# matrix_segmen_shalat_v1_3A.net
KiCad netlist of a schematic drawn in EAGLE
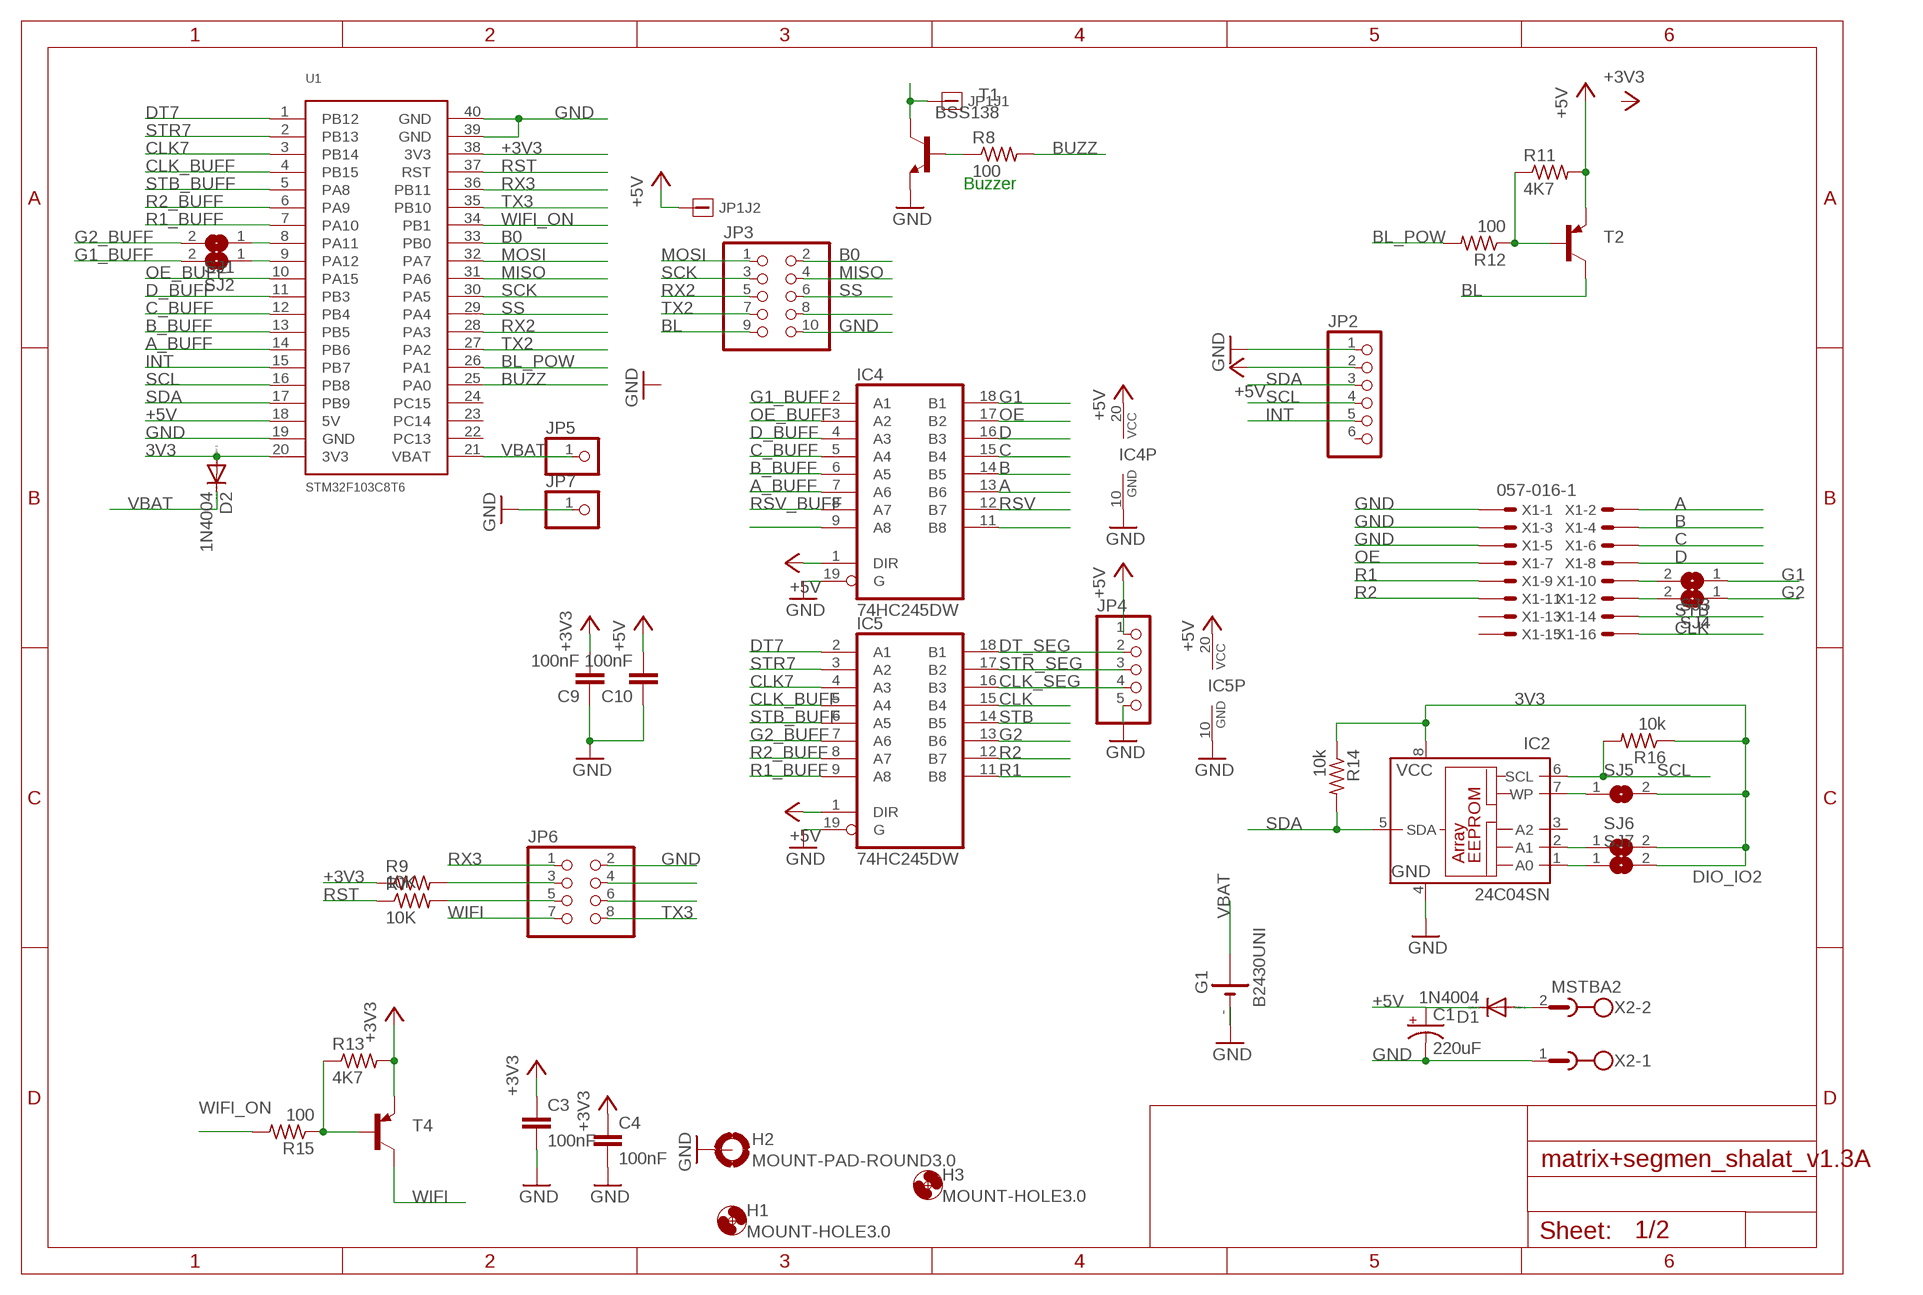
[diagram p0: schematic, sheet 1]
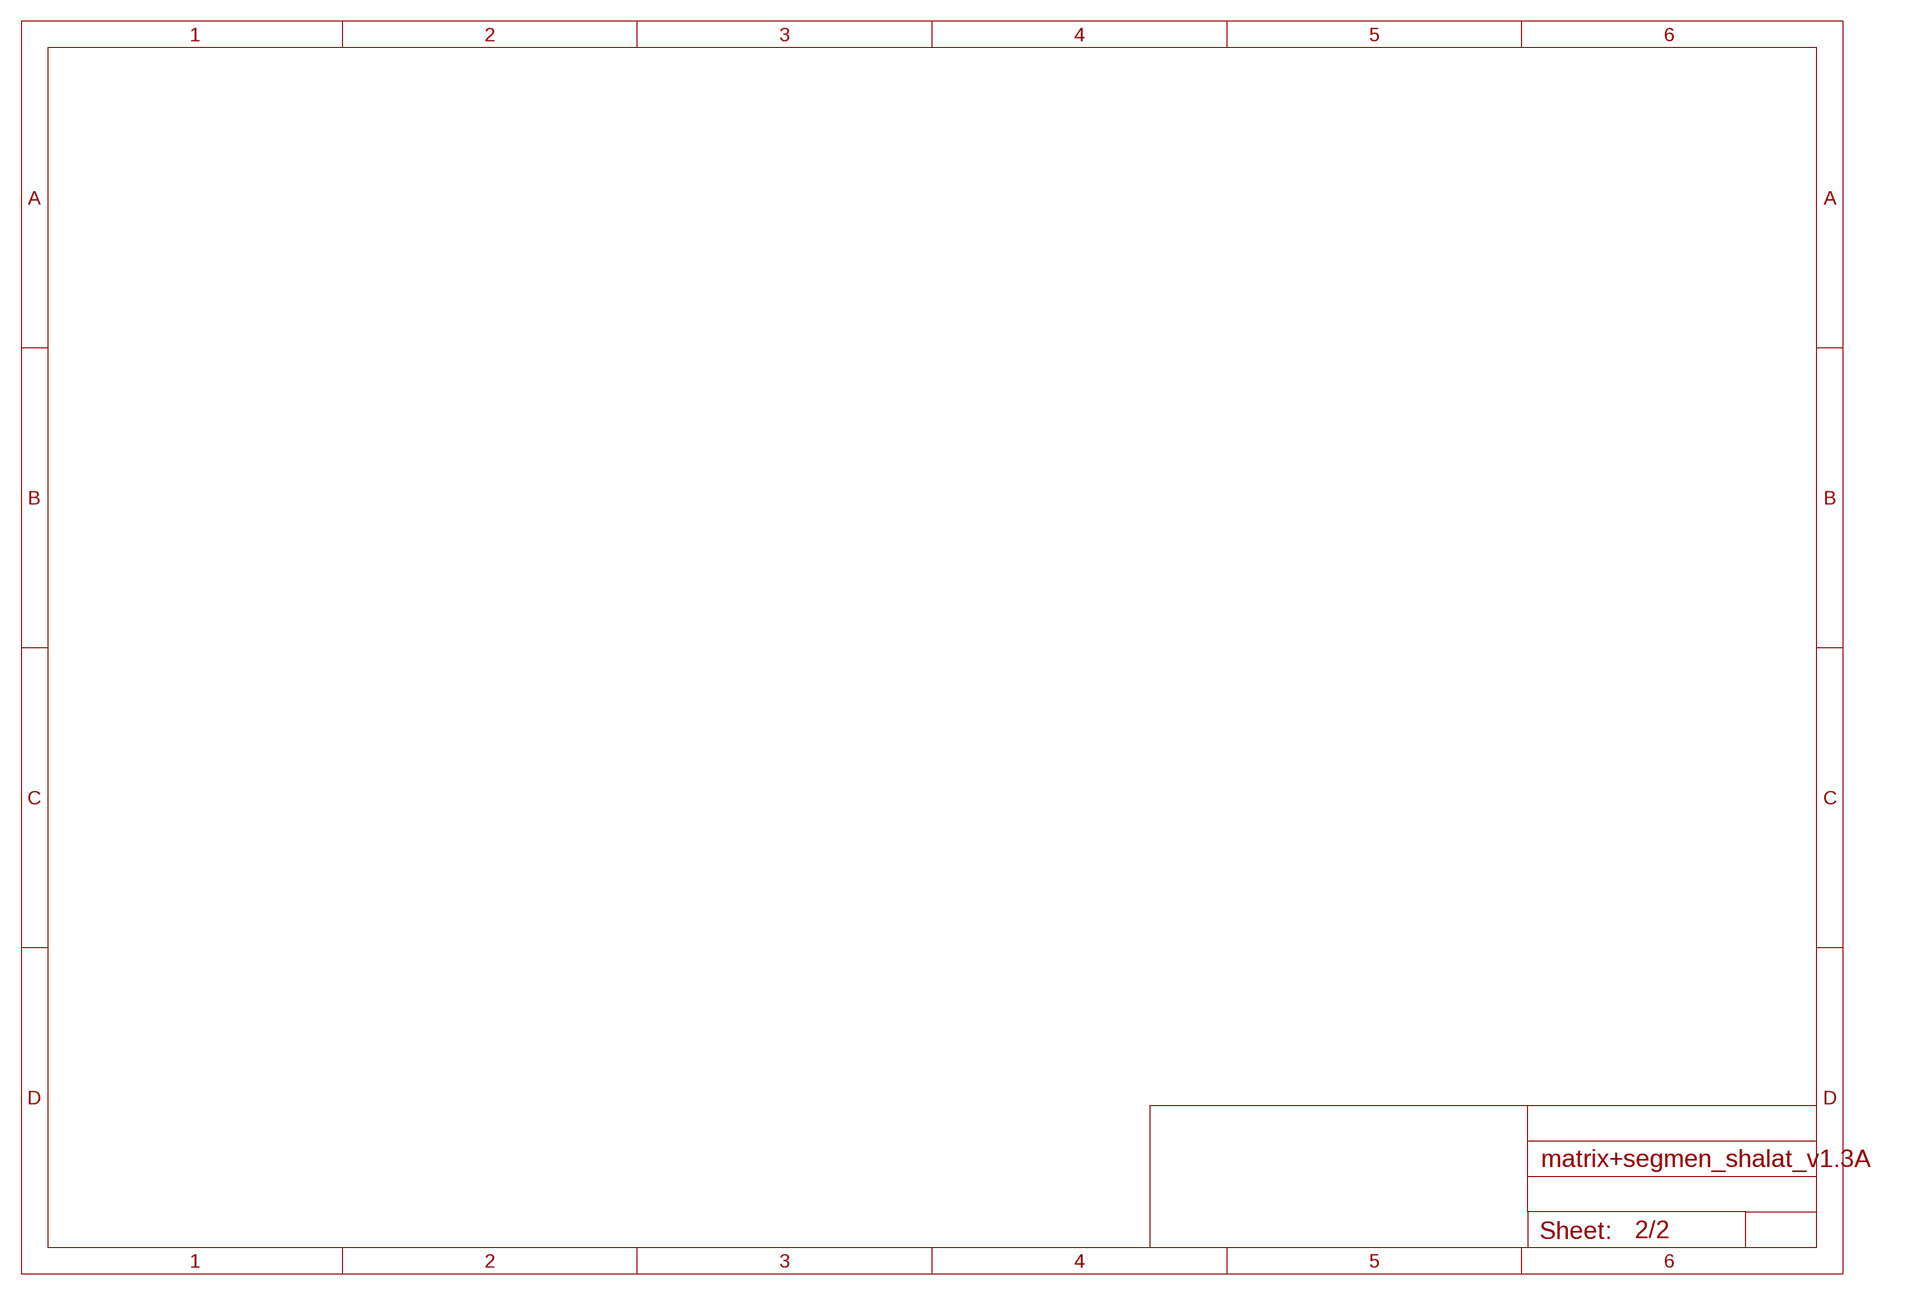
[diagram p1: schematic, sheet 2]

(export (version "E")
  (design (tool "Eeschema 10.0.6"))
  (components
    (comp (ref "C1")
      (value "220uF")
      (footprint "eagle-import:E3,5-8")
      (libsource (lib "eagle-import") (part "CPOL-USE3.5-8"))
    )
    (comp (ref "C3")
      (value "100nF")
      (footprint "eagle-import:C0805")
      (libsource (lib "eagle-import") (part "C-EUC0805"))
    )
    (comp (ref "C4")
      (value "100nF")
      (footprint "eagle-import:C0805")
      (libsource (lib "eagle-import") (part "C-EUC0805"))
    )
    (comp (ref "C9")
      (value "100nF")
      (footprint "eagle-import:C0805")
      (libsource (lib "eagle-import") (part "resistor_C-EUC0805"))
    )
    (comp (ref "C10")
      (value "100nF")
      (footprint "eagle-import:C0805")
      (libsource (lib "eagle-import") (part "resistor_C-EUC0805"))
    )
    (comp (ref "D1")
      (value "1N4004")
      (footprint "eagle-import:DO41-10")
      (libsource (lib "eagle-import") (part "1N4004"))
    )
    (comp (ref "D2")
      (value "1N4004")
      (footprint "eagle-import:DO41-10")
      (libsource (lib "eagle-import") (part "1N4004"))
    )
    (comp (ref "G1")
      (value "B2430UNI")
      (footprint "eagle-import:B2430UNI")
      (libsource (lib "eagle-import") (part "B2430UNI"))
    )
    (comp (ref "H1")
      (value "MOUNT-HOLE3.0")
      (footprint "eagle-import:3,0")
      (libsource (lib "eagle-import") (part "MOUNT-HOLE3.0"))
    )
    (comp (ref "H2")
      (value "MOUNT-PAD-ROUND3.0")
      (footprint "eagle-import:3,0-PAD")
      (libsource (lib "eagle-import") (part "MOUNT-PAD-ROUND3.0"))
    )
    (comp (ref "H3")
      (value "MOUNT-HOLE3.0")
      (footprint "eagle-import:3,0")
      (libsource (lib "eagle-import") (part "MOUNT-HOLE3.0"))
    )
    (comp (ref "IC2")
      (value "24C04SN")
      (footprint "eagle-import:SO-08")
      (fields (field (name "MPN") "M24C04-WMN6P"))
      (libsource (lib "eagle-import") (part "24CSN04"))
    )
    (comp (ref "IC4")
      (value "74HC245DW")
      (footprint "eagle-import:SO20W")
      (libsource (lib "eagle-import") (part "74245DWHC"))
    )
    (comp (ref "IC5")
      (value "74HC245DW")
      (footprint "eagle-import:SO20W")
      (libsource (lib "eagle-import") (part "74245DWHC"))
    )
    (comp (ref "JP1")
      (value "CON2-3.81")
      (footprint "eagle-import:CON2-3.81")
      (libsource (lib "eagle-import") (part "CON2-3.81"))
    )
    (comp (ref "JP2")
      (value "PINHD-1X6")
      (footprint "eagle-import:1X06")
      (libsource (lib "eagle-import") (part "PINHD-1X6"))
    )
    (comp (ref "JP3")
      (value "PINHD-2X5")
      (footprint "eagle-import:2X05")
      (libsource (lib "eagle-import") (part "PINHD-2X5"))
    )
    (comp (ref "JP4")
      (value "PINHD-1X5")
      (footprint "eagle-import:1X05")
      (libsource (lib "eagle-import") (part "PINHD-1X5"))
    )
    (comp (ref "JP5")
      (value "PINHD-1X1")
      (footprint "eagle-import:1X01")
      (libsource (lib "eagle-import") (part "PINHD-1X1"))
    )
    (comp (ref "JP6")
      (value "PINHD-2X4")
      (footprint "eagle-import:2X04")
      (libsource (lib "eagle-import") (part "PINHD-2X4"))
    )
    (comp (ref "JP7")
      (value "PINHD-1X1")
      (footprint "eagle-import:1X01")
      (libsource (lib "eagle-import") (part "PINHD-1X1"))
    )
    (comp (ref "R7")
      (value "10K")
      (footprint "eagle-import:R0805")
      (libsource (lib "eagle-import") (part "R-US_R0805"))
    )
    (comp (ref "R8")
      (value "100")
      (footprint "eagle-import:R0805")
      (libsource (lib "eagle-import") (part "R-US_R0805"))
    )
    (comp (ref "R9")
      (value "10K")
      (footprint "eagle-import:R0805")
      (libsource (lib "eagle-import") (part "R-US_R0805"))
    )
    (comp (ref "R11")
      (value "4K7")
      (footprint "eagle-import:R0805")
      (libsource (lib "eagle-import") (part "R-US_R0805"))
    )
    (comp (ref "R12")
      (value "100")
      (footprint "eagle-import:R0805")
      (libsource (lib "eagle-import") (part "R-US_R0805"))
    )
    (comp (ref "R13")
      (value "4K7")
      (footprint "eagle-import:R0805")
      (libsource (lib "eagle-import") (part "R-US_R0805"))
    )
    (comp (ref "R14")
      (value "10k")
      (footprint "eagle-import:R0805")
      (libsource (lib "eagle-import") (part "R-US_R0805"))
    )
    (comp (ref "R15")
      (value "100")
      (footprint "eagle-import:R0805")
      (libsource (lib "eagle-import") (part "R-US_R0805"))
    )
    (comp (ref "R16")
      (value "10k")
      (footprint "eagle-import:R0805")
      (libsource (lib "eagle-import") (part "R-US_R0805"))
    )
    (comp (ref "SJ1")
      (value "SJ")
      (footprint "eagle-import:SJ")
      (libsource (lib "eagle-import") (part "jumper_252_SJ"))
    )
    (comp (ref "SJ2")
      (value "SJ")
      (footprint "eagle-import:SJ")
      (libsource (lib "eagle-import") (part "jumper_252_SJ"))
    )
    (comp (ref "SJ3")
      (value "SJ")
      (footprint "eagle-import:SJ")
      (libsource (lib "eagle-import") (part "jumper_252_SJ"))
    )
    (comp (ref "SJ4")
      (value "SJ")
      (footprint "eagle-import:SJ")
      (libsource (lib "eagle-import") (part "jumper_252_SJ"))
    )
    (comp (ref "SJ5") (value "SJ") (footprint "eagle-import:SJ") (libsource (lib "eagle-import") (part "SJ")))
    (comp (ref "SJ6") (value "SJ") (footprint "eagle-import:SJ") (libsource (lib "eagle-import") (part "SJ")))
    (comp (ref "SJ7") (value "SJ") (footprint "eagle-import:SJ") (libsource (lib "eagle-import") (part "SJ")))
    (comp (ref "T1")
      (value "BSS138")
      (footprint "eagle-import:SOT23-BEC")
      (libsource (lib "eagle-import") (part "-NPN-SOT23-BECMMBT2222ALT1"))
    )
    (comp (ref "T2")
      (value "-PNP-TO126V")
      (footprint "eagle-import:TO126V")
      (libsource (lib "eagle-import") (part "-PNP-TO126V"))
    )
    (comp (ref "T4")
      (value "-PNP-TO126V")
      (footprint "eagle-import:TO126V")
      (libsource (lib "eagle-import") (part "-PNP-TO126V"))
    )
    (comp (ref "U1")
      (value "STM32F103C8T6")
      (footprint "eagle-import:STM32F103")
      (libsource (lib "eagle-import") (part "STM32F103C8T6"))
    )
    (comp (ref "X1")
      (value "057-016-1")
      (footprint "eagle-import:057-016-1")
      (libsource (lib "eagle-import") (part "057-016-1"))
    )
    (comp (ref "X2")
      (value "MSTBA2")
      (footprint "eagle-import:MSTBA2")
      (fields (field (name "MF") "FARNELL") (field (name "MPN") "1757242"))
      (libsource (lib "eagle-import") (part "MSTBA2"))
    )
  )
  (nets
    (net (code "1") (name "+3V3") (class "Default")
      (node (ref "C3") (pin "1") (pinfunction "1_1") (pintype "passive"))
      (node (ref "C4") (pin "1") (pinfunction "1_1") (pintype "passive"))
      (node (ref "C9") (pin "2") (pinfunction "2_2") (pintype "passive"))
      (node (ref "R13") (pin "2") (pinfunction "2_2") (pintype "passive"))
      (node (ref "R9") (pin "1") (pinfunction "1_1") (pintype "passive"))
      (node (ref "T4") (pin "1") (pinfunction "E_1") (pintype "passive"))
      (node (ref "U1") (pin "38") (pinfunction "3V3_38") (pintype "bidirectional"))
    )
    (net (code "2") (name "+5V") (class "Default")
      (node (ref "C1") (pin "+") (pinfunction "+_+") (pintype "passive"))
      (node (ref "C10") (pin "2") (pinfunction "2_2") (pintype "passive"))
      (node (ref "D1") (pin "C") (pinfunction "C_C") (pintype "passive"))
      (node (ref "IC4") (pin "1") (pinfunction "DIR_1") (pintype "input"))
      (node (ref "IC4") (pin "20") (pinfunction "VCC_20") (pintype "power_in"))
      (node (ref "IC5") (pin "1") (pinfunction "DIR_1") (pintype "input"))
      (node (ref "IC5") (pin "20") (pinfunction "VCC_20") (pintype "power_in"))
      (node (ref "JP1") (pin "2") (pinfunction "1_2") (pintype "passive"))
      (node (ref "JP2") (pin "2") (pinfunction "2_2") (pintype "passive"))
      (node (ref "JP4") (pin "1") (pinfunction "1_1") (pintype "passive"))
      (node (ref "R11") (pin "2") (pinfunction "2_2") (pintype "passive"))
      (node (ref "T2") (pin "1") (pinfunction "E_1") (pintype "passive"))
      (node (ref "U1") (pin "18") (pinfunction "5V_18") (pintype "bidirectional"))
    )
    (net (code "3") (name "3V3") (class "Default")
      (node (ref "D2") (pin "A") (pinfunction "A_A") (pintype "passive"))
      (node (ref "IC2") (pin "8") (pinfunction "VCC_8") (pintype "power_in"))
      (node (ref "R14") (pin "1") (pinfunction "1_1") (pintype "passive"))
      (node (ref "R16") (pin "1") (pinfunction "1_1") (pintype "passive"))
      (node (ref "SJ5") (pin "2") (pinfunction "2_2") (pintype "passive"))
      (node (ref "SJ6") (pin "2") (pinfunction "2_2") (pintype "passive"))
      (node (ref "SJ7") (pin "2") (pinfunction "2_2") (pintype "passive"))
      (node (ref "U1") (pin "20") (pinfunction "3V3_20") (pintype "bidirectional"))
    )
    (net (code "4") (name "A") (class "Default")
      (node (ref "IC4") (pin "13") (pinfunction "B6_13") (pintype "bidirectional"))
      (node (ref "X1") (pin "2") (pinfunction "S_2") (pintype "passive"))
    )
    (net (code "5") (name "A_BUFF") (class "Default")
      (node (ref "IC4") (pin "7") (pinfunction "A6_7") (pintype "bidirectional"))
      (node (ref "U1") (pin "14") (pinfunction "PB6_14") (pintype "bidirectional"))
    )
    (net (code "6") (name "B") (class "Default")
      (node (ref "IC4") (pin "14") (pinfunction "B5_14") (pintype "bidirectional"))
      (node (ref "X1") (pin "4") (pinfunction "S_4") (pintype "passive"))
    )
    (net (code "7") (name "B0") (class "Default")
      (node (ref "JP3") (pin "2") (pinfunction "2_2") (pintype "passive"))
      (node (ref "U1") (pin "33") (pinfunction "PB0_33") (pintype "bidirectional"))
    )
    (net (code "8") (name "BL") (class "Default")
      (node (ref "JP3") (pin "9") (pinfunction "9_9") (pintype "passive"))
      (node (ref "T2") (pin "2") (pinfunction "C_2") (pintype "passive"))
    )
    (net (code "9") (name "BL_POW") (class "Default")
      (node (ref "R12") (pin "2") (pinfunction "2_2") (pintype "passive"))
      (node (ref "U1") (pin "26") (pinfunction "PA1_26") (pintype "bidirectional"))
    )
    (net (code "10") (name "BUZZ") (class "Default")
      (node (ref "R8") (pin "2") (pinfunction "2_2") (pintype "passive"))
      (node (ref "U1") (pin "25") (pinfunction "PA0_25") (pintype "bidirectional"))
    )
    (net (code "11") (name "B_BUFF") (class "Default")
      (node (ref "IC4") (pin "6") (pinfunction "A5_6") (pintype "bidirectional"))
      (node (ref "U1") (pin "13") (pinfunction "PB5_13") (pintype "bidirectional"))
    )
    (net (code "12") (name "C") (class "Default")
      (node (ref "IC4") (pin "15") (pinfunction "B4_15") (pintype "bidirectional"))
      (node (ref "X1") (pin "6") (pinfunction "S_6") (pintype "passive"))
    )
    (net (code "13") (name "CLK") (class "Default")
      (node (ref "IC5") (pin "15") (pinfunction "B4_15") (pintype "bidirectional"))
      (node (ref "X1") (pin "16") (pinfunction "S_16") (pintype "passive"))
    )
    (net (code "14") (name "CLK7") (class "Default")
      (node (ref "IC5") (pin "4") (pinfunction "A3_4") (pintype "bidirectional"))
      (node (ref "U1") (pin "3") (pinfunction "PB14_3") (pintype "bidirectional"))
    )
    (net (code "15") (name "CLK_BUFF") (class "Default")
      (node (ref "IC5") (pin "5") (pinfunction "A4_5") (pintype "bidirectional"))
      (node (ref "U1") (pin "4") (pinfunction "PB15_4") (pintype "bidirectional"))
    )
    (net (code "16") (name "CLK_SEG") (class "Default")
      (node (ref "IC5") (pin "16") (pinfunction "B3_16") (pintype "bidirectional"))
      (node (ref "JP4") (pin "4") (pinfunction "4_4") (pintype "passive"))
    )
    (net (code "17") (name "C_BUFF") (class "Default")
      (node (ref "IC4") (pin "5") (pinfunction "A4_5") (pintype "bidirectional"))
      (node (ref "U1") (pin "12") (pinfunction "PB4_12") (pintype "bidirectional"))
    )
    (net (code "18") (name "D") (class "Default")
      (node (ref "IC4") (pin "16") (pinfunction "B3_16") (pintype "bidirectional"))
      (node (ref "X1") (pin "8") (pinfunction "S_8") (pintype "passive"))
    )
    (net (code "20") (name "DT7") (class "Default")
      (node (ref "IC5") (pin "2") (pinfunction "A1_2") (pintype "bidirectional"))
      (node (ref "U1") (pin "1") (pinfunction "PB12_1") (pintype "bidirectional"))
    )
    (net (code "21") (name "DT_SEG") (class "Default")
      (node (ref "IC5") (pin "18") (pinfunction "B1_18") (pintype "bidirectional"))
      (node (ref "JP4") (pin "2") (pinfunction "2_2") (pintype "passive"))
    )
    (net (code "22") (name "D_BUFF") (class "Default")
      (node (ref "IC4") (pin "4") (pinfunction "A3_4") (pintype "bidirectional"))
      (node (ref "U1") (pin "11") (pinfunction "PB3_11") (pintype "bidirectional"))
    )
    (net (code "23") (name "G1") (class "Default")
      (node (ref "IC4") (pin "18") (pinfunction "B1_18") (pintype "bidirectional"))
      (node (ref "SJ3") (pin "1") (pinfunction "1_1") (pintype "passive"))
    )
    (net (code "24") (name "G1_BUFF") (class "Default")
      (node (ref "IC4") (pin "2") (pinfunction "A1_2") (pintype "bidirectional"))
      (node (ref "SJ2") (pin "2") (pinfunction "2_2") (pintype "passive"))
    )
    (net (code "25") (name "G2") (class "Default")
      (node (ref "IC5") (pin "13") (pinfunction "B6_13") (pintype "bidirectional"))
      (node (ref "SJ4") (pin "1") (pinfunction "1_1") (pintype "passive"))
    )
    (net (code "26") (name "G2_BUFF") (class "Default")
      (node (ref "IC5") (pin "7") (pinfunction "A6_7") (pintype "bidirectional"))
      (node (ref "SJ1") (pin "2") (pinfunction "2_2") (pintype "passive"))
    )
    (net (code "27") (name "GND") (class "Default")
      (node (ref "C1") (pin "-") (pinfunction "-_-") (pintype "passive"))
      (node (ref "C10") (pin "1") (pinfunction "1_1") (pintype "passive"))
      (node (ref "C3") (pin "2") (pinfunction "2_2") (pintype "passive"))
      (node (ref "C4") (pin "2") (pinfunction "2_2") (pintype "passive"))
      (node (ref "C9") (pin "1") (pinfunction "1_1") (pintype "passive"))
      (node (ref "G1") (pin "-") (pinfunction "-_-") (pintype "passive"))
      (node (ref "G1") (pin "-@1") (pinfunction "-_-@1") (pintype "passive"))
      (node (ref "H2") (pin "B3,0") (pinfunction "MOUNT_B3,0") (pintype "passive"))
      (node (ref "IC2") (pin "4") (pinfunction "GND_4") (pintype "power_in"))
      (node (ref "IC4") (pin "10") (pinfunction "GND_10") (pintype "power_in"))
      (node (ref "IC4") (pin "19") (pinfunction "G_19") (pintype "input"))
      (node (ref "IC5") (pin "10") (pinfunction "GND_10") (pintype "power_in"))
      (node (ref "IC5") (pin "19") (pinfunction "G_19") (pintype "input"))
      (node (ref "JP2") (pin "1") (pinfunction "1_1") (pintype "passive"))
      (node (ref "JP3") (pin "10") (pinfunction "10_10") (pintype "passive"))
      (node (ref "JP4") (pin "5") (pinfunction "5_5") (pintype "passive"))
      (node (ref "JP6") (pin "2") (pinfunction "2_2") (pintype "passive"))
      (node (ref "JP7") (pin "1") (pinfunction "1_1") (pintype "passive"))
      (node (ref "T1") (pin "E") (pinfunction "E_E") (pintype "passive"))
      (node (ref "U1") (pin "19") (pinfunction "GND_19") (pintype "bidirectional"))
      (node (ref "U1") (pin "39") (pinfunction "GND_39") (pintype "bidirectional"))
      (node (ref "U1") (pin "40") (pinfunction "GND_40") (pintype "bidirectional"))
      (node (ref "X1") (pin "1") (pinfunction "S_1") (pintype "passive"))
      (node (ref "X1") (pin "3") (pinfunction "S_3") (pintype "passive"))
      (node (ref "X1") (pin "5") (pinfunction "S_5") (pintype "passive"))
      (node (ref "X2") (pin "1") (pinfunction "1_1") (pintype "passive"))
    )
    (net (code "28") (name "INT") (class "Default")
      (node (ref "JP2") (pin "5") (pinfunction "5_5") (pintype "passive"))
      (node (ref "U1") (pin "15") (pinfunction "PB7_15") (pintype "bidirectional"))
    )
    (net (code "29") (name "MISO") (class "Default")
      (node (ref "JP3") (pin "4") (pinfunction "4_4") (pintype "passive"))
      (node (ref "U1") (pin "31") (pinfunction "PA6_31") (pintype "bidirectional"))
    )
    (net (code "30") (name "MOSI") (class "Default")
      (node (ref "JP3") (pin "1") (pinfunction "1_1") (pintype "passive"))
      (node (ref "U1") (pin "32") (pinfunction "PA7_32") (pintype "bidirectional"))
    )
    (net (code "31") (name "Net-(IC2-A0)") (class "Default")
      (node (ref "IC2") (pin "1") (pinfunction "A0_1") (pintype "input"))
      (node (ref "SJ7") (pin "1") (pinfunction "1_1") (pintype "passive"))
    )
    (net (code "32") (name "Net-(IC2-A1)") (class "Default")
      (node (ref "IC2") (pin "2") (pinfunction "A1_2") (pintype "input"))
      (node (ref "SJ6") (pin "1") (pinfunction "1_1") (pintype "passive"))
    )
    (net (code "33") (name "Net-(IC2-WP)") (class "Default")
      (node (ref "IC2") (pin "7") (pinfunction "WP_7") (pintype "input"))
      (node (ref "SJ5") (pin "1") (pinfunction "1_1") (pintype "passive"))
    )
    (net (code "34") (name "Net-(JP1-Pad1)") (class "Default")
      (node (ref "JP1") (pin "1") (pinfunction "1_1") (pintype "passive"))
      (node (ref "T1") (pin "C") (pinfunction "C_C") (pintype "passive"))
    )
    (net (code "35") (name "Net-(JP6-Pad3)") (class "Default")
      (node (ref "JP6") (pin "3") (pinfunction "3_3") (pintype "passive"))
      (node (ref "R9") (pin "2") (pinfunction "2_2") (pintype "passive"))
    )
    (net (code "36") (name "Net-(JP6-Pad5)") (class "Default")
      (node (ref "JP6") (pin "5") (pinfunction "5_5") (pintype "passive"))
      (node (ref "R7") (pin "2") (pinfunction "2_2") (pintype "passive"))
    )
    (net (code "37") (name "Net-(R8-Pad1)") (class "Default")
      (node (ref "R8") (pin "1") (pinfunction "1_1") (pintype "passive"))
      (node (ref "T1") (pin "B") (pinfunction "B_B") (pintype "passive"))
    )
    (net (code "38") (name "Net-(T2-B)") (class "Default")
      (node (ref "R11") (pin "1") (pinfunction "1_1") (pintype "passive"))
      (node (ref "R12") (pin "1") (pinfunction "1_1") (pintype "passive"))
      (node (ref "T2") (pin "3") (pinfunction "B_3") (pintype "passive"))
    )
    (net (code "39") (name "Net-(T4-B)") (class "Default")
      (node (ref "R13") (pin "1") (pinfunction "1_1") (pintype "passive"))
      (node (ref "R15") (pin "1") (pinfunction "1_1") (pintype "passive"))
      (node (ref "T4") (pin "3") (pinfunction "B_3") (pintype "passive"))
    )
    (net (code "40") (name "Net-(U1-PA11)") (class "Default")
      (node (ref "SJ1") (pin "1") (pinfunction "1_1") (pintype "passive"))
      (node (ref "U1") (pin "8") (pinfunction "PA11_8") (pintype "bidirectional"))
    )
    (net (code "41") (name "Net-(U1-PA12)") (class "Default")
      (node (ref "SJ2") (pin "1") (pinfunction "1_1") (pintype "passive"))
      (node (ref "U1") (pin "9") (pinfunction "PA12_9") (pintype "bidirectional"))
    )
    (net (code "42") (name "Net-(X1B-S)") (class "Default")
      (node (ref "SJ3") (pin "2") (pinfunction "2_2") (pintype "passive"))
      (node (ref "X1") (pin "10") (pinfunction "S_10") (pintype "passive"))
    )
    (net (code "43") (name "Net-(X1D-S)") (class "Default")
      (node (ref "SJ4") (pin "2") (pinfunction "2_2") (pintype "passive"))
      (node (ref "X1") (pin "12") (pinfunction "S_12") (pintype "passive"))
    )
    (net (code "44") (name "Net-(X2B-1)") (class "Default")
      (node (ref "D1") (pin "A") (pinfunction "A_A") (pintype "passive"))
      (node (ref "X2") (pin "2") (pinfunction "1_2") (pintype "passive"))
    )
    (net (code "45") (name "OE") (class "Default")
      (node (ref "IC4") (pin "17") (pinfunction "B2_17") (pintype "bidirectional"))
      (node (ref "X1") (pin "7") (pinfunction "S_7") (pintype "passive"))
    )
    (net (code "46") (name "OE_BUFF") (class "Default")
      (node (ref "IC4") (pin "3") (pinfunction "A2_3") (pintype "bidirectional"))
      (node (ref "U1") (pin "10") (pinfunction "PA15_10") (pintype "bidirectional"))
    )
    (net (code "47") (name "R1") (class "Default")
      (node (ref "IC5") (pin "11") (pinfunction "B8_11") (pintype "bidirectional"))
      (node (ref "X1") (pin "9") (pinfunction "S_9") (pintype "passive"))
    )
    (net (code "48") (name "R1_BUFF") (class "Default")
      (node (ref "IC5") (pin "9") (pinfunction "A8_9") (pintype "bidirectional"))
      (node (ref "U1") (pin "7") (pinfunction "PA10_7") (pintype "bidirectional"))
    )
    (net (code "49") (name "R2") (class "Default")
      (node (ref "IC5") (pin "12") (pinfunction "B7_12") (pintype "bidirectional"))
      (node (ref "X1") (pin "11") (pinfunction "S_11") (pintype "passive"))
    )
    (net (code "50") (name "R2_BUFF") (class "Default")
      (node (ref "IC5") (pin "8") (pinfunction "A7_8") (pintype "bidirectional"))
      (node (ref "U1") (pin "6") (pinfunction "PA9_6") (pintype "bidirectional"))
    )
    (net (code "51") (name "RST") (class "Default")
      (node (ref "R7") (pin "1") (pinfunction "1_1") (pintype "passive"))
      (node (ref "U1") (pin "37") (pinfunction "RST_37") (pintype "bidirectional"))
    )
    (net (code "52") (name "RSV") (class "Default")
      (node (ref "IC4") (pin "12") (pinfunction "B7_12") (pintype "bidirectional"))
    )
    (net (code "53") (name "RSV_BUFF") (class "Default")
      (node (ref "IC4") (pin "8") (pinfunction "A7_8") (pintype "bidirectional"))
    )
    (net (code "54") (name "RX2") (class "Default")
      (node (ref "JP3") (pin "5") (pinfunction "5_5") (pintype "passive"))
      (node (ref "U1") (pin "28") (pinfunction "PA3_28") (pintype "bidirectional"))
    )
    (net (code "55") (name "RX3") (class "Default")
      (node (ref "JP6") (pin "1") (pinfunction "1_1") (pintype "passive"))
      (node (ref "U1") (pin "36") (pinfunction "PB11_36") (pintype "bidirectional"))
    )
    (net (code "56") (name "SCK") (class "Default")
      (node (ref "JP3") (pin "3") (pinfunction "3_3") (pintype "passive"))
      (node (ref "U1") (pin "30") (pinfunction "PA5_30") (pintype "bidirectional"))
    )
    (net (code "57") (name "SCL") (class "Default")
      (node (ref "IC2") (pin "6") (pinfunction "SCL_6") (pintype "input"))
      (node (ref "JP2") (pin "4") (pinfunction "4_4") (pintype "passive"))
      (node (ref "R16") (pin "2") (pinfunction "2_2") (pintype "passive"))
      (node (ref "U1") (pin "16") (pinfunction "PB8_16") (pintype "bidirectional"))
    )
    (net (code "58") (name "SDA") (class "Default")
      (node (ref "IC2") (pin "5") (pinfunction "SDA_5") (pintype "bidirectional"))
      (node (ref "JP2") (pin "3") (pinfunction "3_3") (pintype "passive"))
      (node (ref "R14") (pin "2") (pinfunction "2_2") (pintype "passive"))
      (node (ref "U1") (pin "17") (pinfunction "PB9_17") (pintype "bidirectional"))
    )
    (net (code "59") (name "SS") (class "Default")
      (node (ref "JP3") (pin "6") (pinfunction "6_6") (pintype "passive"))
      (node (ref "U1") (pin "29") (pinfunction "PA4_29") (pintype "bidirectional"))
    )
    (net (code "60") (name "STB") (class "Default")
      (node (ref "IC5") (pin "14") (pinfunction "B5_14") (pintype "bidirectional"))
      (node (ref "X1") (pin "14") (pinfunction "S_14") (pintype "passive"))
    )
    (net (code "61") (name "STB_BUFF") (class "Default")
      (node (ref "IC5") (pin "6") (pinfunction "A5_6") (pintype "bidirectional"))
      (node (ref "U1") (pin "5") (pinfunction "PA8_5") (pintype "bidirectional"))
    )
    (net (code "62") (name "STR7") (class "Default")
      (node (ref "IC5") (pin "3") (pinfunction "A2_3") (pintype "bidirectional"))
      (node (ref "U1") (pin "2") (pinfunction "PB13_2") (pintype "bidirectional"))
    )
    (net (code "63") (name "STR_SEG") (class "Default")
      (node (ref "IC5") (pin "17") (pinfunction "B2_17") (pintype "bidirectional"))
      (node (ref "JP4") (pin "3") (pinfunction "3_3") (pintype "passive"))
    )
    (net (code "64") (name "TX2") (class "Default")
      (node (ref "JP3") (pin "7") (pinfunction "7_7") (pintype "passive"))
      (node (ref "U1") (pin "27") (pinfunction "PA2_27") (pintype "bidirectional"))
    )
    (net (code "65") (name "TX3") (class "Default")
      (node (ref "JP6") (pin "8") (pinfunction "8_8") (pintype "passive"))
      (node (ref "U1") (pin "35") (pinfunction "PB10_35") (pintype "bidirectional"))
    )
    (net (code "66") (name "VBAT") (class "Default")
      (node (ref "D2") (pin "C") (pinfunction "C_C") (pintype "passive"))
      (node (ref "G1") (pin "+@4") (pinfunction "+_+@4") (pintype "passive"))
      (node (ref "JP5") (pin "1") (pinfunction "1_1") (pintype "passive"))
      (node (ref "U1") (pin "21") (pinfunction "VBAT_21") (pintype "bidirectional"))
    )
    (net (code "67") (name "WIFI") (class "Default")
      (node (ref "JP6") (pin "7") (pinfunction "7_7") (pintype "passive"))
      (node (ref "T4") (pin "2") (pinfunction "C_2") (pintype "passive"))
    )
    (net (code "68") (name "WIFI_ON") (class "Default")
      (node (ref "R15") (pin "2") (pinfunction "2_2") (pintype "passive"))
      (node (ref "U1") (pin "34") (pinfunction "PB1_34") (pintype "bidirectional"))
    )
    (net (code "69") (name "unconnected-(IC2-A2-Pad3)") (class "Default")
      (node (ref "IC2") (pin "3") (pinfunction "A2_3") (pintype "input"))
    )
    (net (code "70") (name "unconnected-(IC4A-A8-Pad9)") (class "Default")
      (node (ref "IC4") (pin "9") (pinfunction "A8_9") (pintype "bidirectional"))
    )
    (net (code "71") (name "unconnected-(IC4A-B8-Pad11)") (class "Default")
      (node (ref "IC4") (pin "11") (pinfunction "B8_11") (pintype "bidirectional"))
    )
    (net (code "72") (name "unconnected-(JP2-Pad6)") (class "Default")
      (node (ref "JP2") (pin "6") (pinfunction "6_6") (pintype "passive"))
    )
    (net (code "73") (name "unconnected-(JP3-Pad8)") (class "Default")
      (node (ref "JP3") (pin "8") (pinfunction "8_8") (pintype "passive"))
    )
    (net (code "74") (name "unconnected-(JP6-Pad4)") (class "Default")
      (node (ref "JP6") (pin "4") (pinfunction "4_4") (pintype "passive"))
    )
    (net (code "75") (name "unconnected-(JP6-Pad6)") (class "Default")
      (node (ref "JP6") (pin "6") (pinfunction "6_6") (pintype "passive"))
    )
    (net (code "76") (name "unconnected-(U1-PC13-Pad22)") (class "Default")
      (node (ref "U1") (pin "22") (pinfunction "PC13_22") (pintype "bidirectional"))
    )
    (net (code "77") (name "unconnected-(U1-PC14-Pad23)") (class "Default")
      (node (ref "U1") (pin "23") (pinfunction "PC14_23") (pintype "bidirectional"))
    )
    (net (code "78") (name "unconnected-(U1-PC15-Pad24)") (class "Default")
      (node (ref "U1") (pin "24") (pinfunction "PC15_24") (pintype "bidirectional"))
    )
    (net (code "79") (name "unconnected-(X1E-S-Pad13)") (class "Default")
      (node (ref "X1") (pin "13") (pinfunction "S_13") (pintype "passive"))
    )
    (net (code "80") (name "unconnected-(X1G-S-Pad15)") (class "Default")
      (node (ref "X1") (pin "15") (pinfunction "S_15") (pintype "passive"))
    )
  )
)
